# 4BitCounter.net
KiCad netlist of a schematic drawn in EAGLE
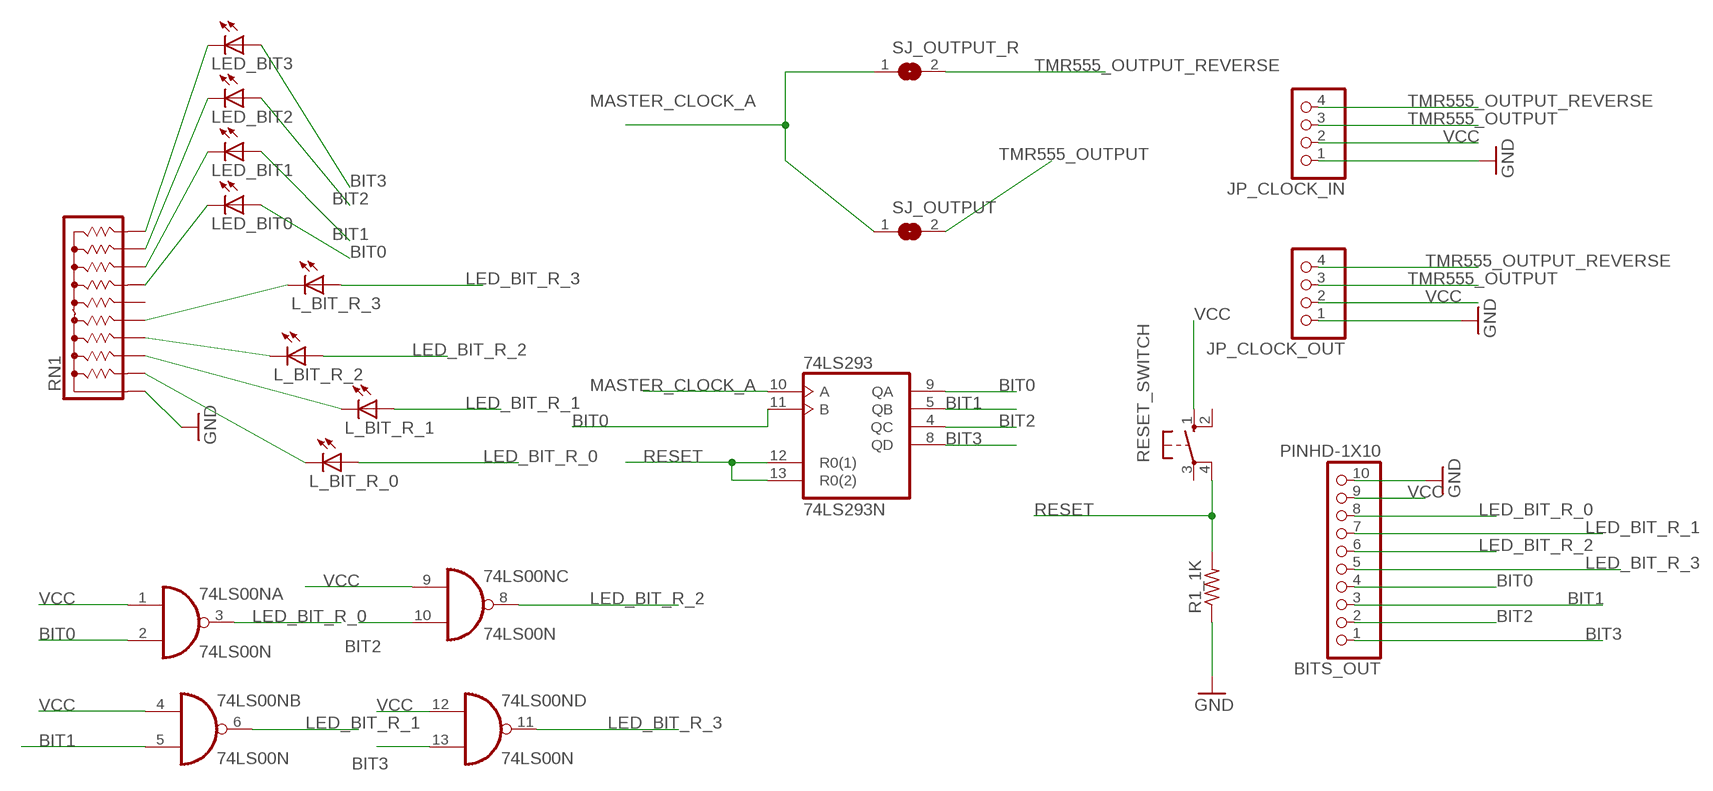
[diagram p0: schematic, sheet 1]

(export (version "E")
  (design (tool "Eeschema 10.0.6"))
  (components
    (comp (ref "74LS00N")
      (value "74LS00N")
      (footprint "eagle-import:DIL14")
      (libsource (lib "eagle-import") (part "7400NLS"))
    )
    (comp (ref "74LS293")
      (value "74LS293N")
      (footprint "eagle-import:DIL14")
      (libsource (lib "eagle-import") (part "74293NLS"))
    )
    (comp (ref "BITS_OUT")
      (value "PINHD-1X10")
      (footprint "eagle-import:1X10-BIG")
      (libsource (lib "eagle-import") (part "PINHD-1X10"))
    )
    (comp (ref "JP_CLOCK_IN")
      (value "PINHD-1X4")
      (footprint "eagle-import:1X04")
      (libsource (lib "eagle-import") (part "PINHD-1X4"))
    )
    (comp (ref "JP_CLOCK_OUT")
      (value "PINHD-1X4")
      (footprint "eagle-import:1X04")
      (libsource (lib "eagle-import") (part "PINHD-1X4"))
    )
    (comp (ref "LED_BIT0")
      (value "LEDSMT1206")
      (footprint "eagle-import:1206")
      (libsource (lib "eagle-import") (part "LEDSMT1206"))
    )
    (comp (ref "LED_BIT1")
      (value "LEDSMT1206")
      (footprint "eagle-import:1206")
      (libsource (lib "eagle-import") (part "LEDSMT1206"))
    )
    (comp (ref "LED_BIT2")
      (value "LEDSMT1206")
      (footprint "eagle-import:1206")
      (libsource (lib "eagle-import") (part "LEDSMT1206"))
    )
    (comp (ref "LED_BIT3")
      (value "LEDSMT1206")
      (footprint "eagle-import:1206")
      (libsource (lib "eagle-import") (part "LEDSMT1206"))
    )
    (comp (ref "L_BIT_R_0")
      (value "LEDSMT1206")
      (footprint "eagle-import:1206")
      (libsource (lib "eagle-import") (part "LEDSMT1206"))
    )
    (comp (ref "L_BIT_R_1")
      (value "LEDSMT1206")
      (footprint "eagle-import:1206")
      (libsource (lib "eagle-import") (part "LEDSMT1206"))
    )
    (comp (ref "L_BIT_R_2")
      (value "LEDSMT1206")
      (footprint "eagle-import:1206")
      (libsource (lib "eagle-import") (part "LEDSMT1206"))
    )
    (comp (ref "L_BIT_R_3")
      (value "LEDSMT1206")
      (footprint "eagle-import:1206")
      (libsource (lib "eagle-import") (part "LEDSMT1206"))
    )
    (comp (ref "R1_1K")
      (value "R-US_R1206")
      (footprint "eagle-import:R1206")
      (libsource (lib "eagle-import") (part "R-US_R1206"))
    )
    (comp (ref "RESET_SWITCH")
      (value "10-XX")
      (footprint "eagle-import:B3F-10XX")
      (fields (field (name "MPN") "B3F-1000"))
      (libsource (lib "eagle-import") (part "10-XX"))
    )
    (comp (ref "RN1")
      (value "4610X")
      (footprint "eagle-import:SIP10")
      (libsource (lib "eagle-import") (part "4610X"))
    )
    (comp (ref "SJ_OUTPUT")
      (value "SOLDERJUMPERREFLOW")
      (footprint "eagle-import:SOLDERJUMPER_REFLOW")
      (libsource (lib "eagle-import") (part "SOLDERJUMPERREFLOW"))
    )
    (comp (ref "SJ_OUTPUT_R")
      (value "SOLDERJUMPERREFLOW")
      (footprint "eagle-import:SOLDERJUMPER_REFLOW")
      (libsource (lib "eagle-import") (part "SOLDERJUMPERREFLOW"))
    )
  )
  (nets
    (net (code "1") (name "/BIT0") (class "Default")
      (node (ref "74LS00N") (pin "2") (pinfunction "I1_2") (pintype "input"))
      (node (ref "74LS293") (pin "11") (pinfunction "B_11") (pintype "input"))
      (node (ref "74LS293") (pin "9") (pinfunction "QA_9") (pintype "output"))
      (node (ref "BITS_OUT") (pin "4") (pinfunction "4_4") (pintype "passive"))
      (node (ref "LED_BIT0") (pin "A") (pinfunction "A_A") (pintype "passive"))
    )
    (net (code "2") (name "/BIT1") (class "Default")
      (node (ref "74LS00N") (pin "5") (pinfunction "I1_5") (pintype "input"))
      (node (ref "74LS293") (pin "5") (pinfunction "QB_5") (pintype "output"))
      (node (ref "BITS_OUT") (pin "3") (pinfunction "3_3") (pintype "passive"))
      (node (ref "LED_BIT1") (pin "A") (pinfunction "A_A") (pintype "passive"))
    )
    (net (code "3") (name "/BIT2") (class "Default")
      (node (ref "74LS00N") (pin "10") (pinfunction "I1_10") (pintype "input"))
      (node (ref "74LS293") (pin "4") (pinfunction "QC_4") (pintype "output"))
      (node (ref "BITS_OUT") (pin "2") (pinfunction "2_2") (pintype "passive"))
      (node (ref "LED_BIT2") (pin "A") (pinfunction "A_A") (pintype "passive"))
    )
    (net (code "4") (name "/BIT3") (class "Default")
      (node (ref "74LS00N") (pin "13") (pinfunction "I1_13") (pintype "input"))
      (node (ref "74LS293") (pin "8") (pinfunction "QD_8") (pintype "output"))
      (node (ref "BITS_OUT") (pin "1") (pinfunction "1_1") (pintype "passive"))
      (node (ref "LED_BIT3") (pin "A") (pinfunction "A_A") (pintype "passive"))
    )
    (net (code "5") (name "/LED_BIT_R_0") (class "Default")
      (node (ref "74LS00N") (pin "3") (pinfunction "O_3") (pintype "output"))
      (node (ref "BITS_OUT") (pin "8") (pinfunction "8_8") (pintype "passive"))
      (node (ref "L_BIT_R_0") (pin "A") (pinfunction "A_A") (pintype "passive"))
    )
    (net (code "6") (name "/LED_BIT_R_1") (class "Default")
      (node (ref "74LS00N") (pin "6") (pinfunction "O_6") (pintype "output"))
      (node (ref "BITS_OUT") (pin "7") (pinfunction "7_7") (pintype "passive"))
      (node (ref "L_BIT_R_1") (pin "A") (pinfunction "A_A") (pintype "passive"))
    )
    (net (code "7") (name "/LED_BIT_R_2") (class "Default")
      (node (ref "74LS00N") (pin "8") (pinfunction "O_8") (pintype "output"))
      (node (ref "BITS_OUT") (pin "6") (pinfunction "6_6") (pintype "passive"))
      (node (ref "L_BIT_R_2") (pin "A") (pinfunction "A_A") (pintype "passive"))
    )
    (net (code "8") (name "/LED_BIT_R_3") (class "Default")
      (node (ref "74LS00N") (pin "11") (pinfunction "O_11") (pintype "output"))
      (node (ref "BITS_OUT") (pin "5") (pinfunction "5_5") (pintype "passive"))
      (node (ref "L_BIT_R_3") (pin "A") (pinfunction "A_A") (pintype "passive"))
    )
    (net (code "9") (name "/MASTER_CLOCK_A") (class "Default")
      (node (ref "74LS293") (pin "10") (pinfunction "A_10") (pintype "input"))
      (node (ref "SJ_OUTPUT") (pin "1") (pinfunction "1_1") (pintype "passive"))
      (node (ref "SJ_OUTPUT_R") (pin "1") (pinfunction "1_1") (pintype "passive"))
    )
    (net (code "10") (name "/RESET") (class "Default")
      (node (ref "74LS293") (pin "12") (pinfunction "R0(1)_12") (pintype "input"))
      (node (ref "74LS293") (pin "13") (pinfunction "R0(2)_13") (pintype "input"))
      (node (ref "R1_1K") (pin "2") (pinfunction "2_2") (pintype "passive"))
      (node (ref "RESET_SWITCH") (pin "4") (pinfunction "P1_4") (pintype "passive"))
    )
    (net (code "11") (name "/TMR555_OUTPUT") (class "Default")
      (node (ref "JP_CLOCK_IN") (pin "3") (pinfunction "3_3") (pintype "passive"))
      (node (ref "JP_CLOCK_OUT") (pin "3") (pinfunction "3_3") (pintype "passive"))
      (node (ref "SJ_OUTPUT") (pin "2") (pinfunction "2_2") (pintype "passive"))
    )
    (net (code "12") (name "/TMR555_OUTPUT_REVERSE") (class "Default")
      (node (ref "JP_CLOCK_IN") (pin "4") (pinfunction "4_4") (pintype "passive"))
      (node (ref "JP_CLOCK_OUT") (pin "4") (pinfunction "4_4") (pintype "passive"))
      (node (ref "SJ_OUTPUT_R") (pin "2") (pinfunction "2_2") (pintype "passive"))
    )
    (net (code "13") (name "/VCC") (class "Default")
      (node (ref "74LS00N") (pin "1") (pinfunction "I0_1") (pintype "input"))
      (node (ref "74LS00N") (pin "12") (pinfunction "I0_12") (pintype "input"))
      (node (ref "74LS00N") (pin "4") (pinfunction "I0_4") (pintype "input"))
      (node (ref "74LS00N") (pin "9") (pinfunction "I0_9") (pintype "input"))
      (node (ref "BITS_OUT") (pin "9") (pinfunction "9_9") (pintype "passive"))
      (node (ref "JP_CLOCK_IN") (pin "2") (pinfunction "2_2") (pintype "passive"))
      (node (ref "JP_CLOCK_OUT") (pin "2") (pinfunction "2_2") (pintype "passive"))
      (node (ref "RESET_SWITCH") (pin "1") (pinfunction "S_1") (pintype "passive"))
    )
    (net (code "14") (name "GND") (class "Default")
      (node (ref "BITS_OUT") (pin "10") (pinfunction "10_10") (pintype "passive"))
      (node (ref "JP_CLOCK_IN") (pin "1") (pinfunction "1_1") (pintype "passive"))
      (node (ref "JP_CLOCK_OUT") (pin "1") (pinfunction "1_1") (pintype "passive"))
      (node (ref "R1_1K") (pin "1") (pinfunction "1_1") (pintype "passive"))
      (node (ref "RN1") (pin "1") (pinfunction "1_1") (pintype "passive"))
    )
    (net (code "15") (name "Net-(LED_BIT0-PadC)") (class "Default")
      (node (ref "LED_BIT0") (pin "C") (pinfunction "C_C") (pintype "passive"))
      (node (ref "RN1") (pin "7") (pinfunction "7_7") (pintype "passive"))
    )
    (net (code "16") (name "Net-(LED_BIT1-PadC)") (class "Default")
      (node (ref "LED_BIT1") (pin "C") (pinfunction "C_C") (pintype "passive"))
      (node (ref "RN1") (pin "8") (pinfunction "8_8") (pintype "passive"))
    )
    (net (code "17") (name "Net-(LED_BIT2-PadC)") (class "Default")
      (node (ref "LED_BIT2") (pin "C") (pinfunction "C_C") (pintype "passive"))
      (node (ref "RN1") (pin "9") (pinfunction "9_9") (pintype "passive"))
    )
    (net (code "18") (name "Net-(LED_BIT3-PadC)") (class "Default")
      (node (ref "LED_BIT3") (pin "C") (pinfunction "C_C") (pintype "passive"))
      (node (ref "RN1") (pin "10") (pinfunction "10_10") (pintype "passive"))
    )
    (net (code "19") (name "Net-(L_BIT_R_0-PadC)") (class "Default")
      (node (ref "L_BIT_R_0") (pin "C") (pinfunction "C_C") (pintype "passive"))
      (node (ref "RN1") (pin "2") (pinfunction "2_2") (pintype "passive"))
    )
    (net (code "20") (name "Net-(L_BIT_R_1-PadC)") (class "Default")
      (node (ref "L_BIT_R_1") (pin "C") (pinfunction "C_C") (pintype "passive"))
      (node (ref "RN1") (pin "3") (pinfunction "3_3") (pintype "passive"))
    )
    (net (code "21") (name "Net-(L_BIT_R_2-PadC)") (class "Default")
      (node (ref "L_BIT_R_2") (pin "C") (pinfunction "C_C") (pintype "passive"))
      (node (ref "RN1") (pin "4") (pinfunction "4_4") (pintype "passive"))
    )
    (net (code "22") (name "Net-(L_BIT_R_3-PadC)") (class "Default")
      (node (ref "L_BIT_R_3") (pin "C") (pinfunction "C_C") (pintype "passive"))
      (node (ref "RN1") (pin "5") (pinfunction "5_5") (pintype "passive"))
    )
    (net (code "23") (name "unconnected-(RESET_SWITCH-P-Pad3)") (class "Default")
      (node (ref "RESET_SWITCH") (pin "3") (pinfunction "P_3") (pintype "passive"))
    )
    (net (code "24") (name "unconnected-(RESET_SWITCH-S1-Pad2)") (class "Default")
      (node (ref "RESET_SWITCH") (pin "2") (pinfunction "S1_2") (pintype "passive"))
    )
    (net (code "25") (name "unconnected-(RN1-Pad6)") (class "Default")
      (node (ref "RN1") (pin "6") (pinfunction "6_6") (pintype "passive"))
    )
  )
)
